# p3-001.net
KiCad netlist of a schematic drawn in EAGLE
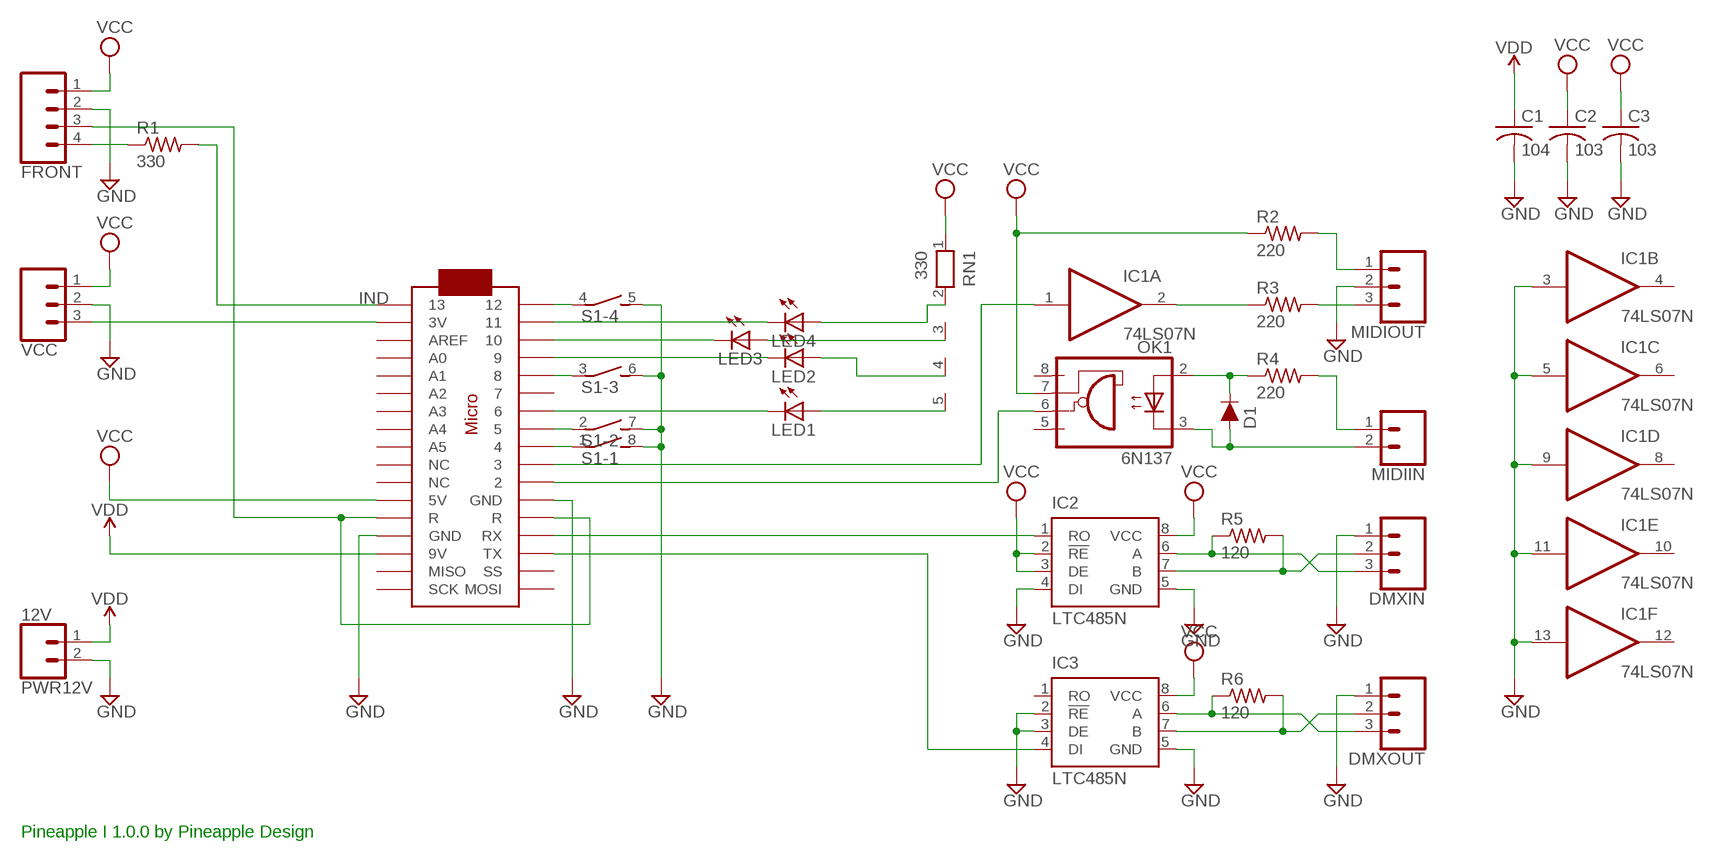
[diagram p0: schematic, sheet 1]

(export (version "E")
  (design (tool "Eeschema 10.0.6"))
  (components
    (comp (ref "C1")
      (value "104")
      (footprint "eagle-import:C025-025X050")
      (libsource (lib "eagle-import") (part "C-US025-025X050"))
    )
    (comp (ref "C2")
      (value "103")
      (footprint "eagle-import:C025-025X050")
      (libsource (lib "eagle-import") (part "C-US025-025X050"))
    )
    (comp (ref "C3")
      (value "103")
      (footprint "eagle-import:C025-025X050")
      (libsource (lib "eagle-import") (part "C-US025-025X050"))
    )
    (comp (ref "D1")
      (value "DIODE-1N4148")
      (footprint "eagle-import:DIODE-1N4148")
      (libsource (lib "eagle-import") (part "DIODE-1N4148"))
    )
    (comp (ref "DMXIN")
      (value "CONN_03JST-PTH")
      (footprint "eagle-import:JST-3-PTH")
      (libsource (lib "eagle-import") (part "CONN_03JST-PTH"))
    )
    (comp (ref "DMXOUT")
      (value "CONN_03JST-PTH")
      (footprint "eagle-import:JST-3-PTH")
      (libsource (lib "eagle-import") (part "CONN_03JST-PTH"))
    )
    (comp (ref "FRONT")
      (value "CONN_04JST-PTH")
      (footprint "eagle-import:JST-4-PTH")
      (libsource (lib "eagle-import") (part "CONN_04JST-PTH"))
    )
    (comp (ref "IC1")
      (value "74LS07N")
      (footprint "eagle-import:DIL14")
      (libsource (lib "eagle-import") (part "7407NLS"))
    )
    (comp (ref "IC2")
      (value "LTC485N")
      (footprint "eagle-import:DIL08")
      (libsource (lib "eagle-import") (part "LTC485N"))
    )
    (comp (ref "IC3")
      (value "LTC485N")
      (footprint "eagle-import:DIL08")
      (libsource (lib "eagle-import") (part "LTC485N"))
    )
    (comp (ref "LED1")
      (value "LED3MM")
      (footprint "eagle-import:LED3MM")
      (libsource (lib "eagle-import") (part "LED3MM"))
    )
    (comp (ref "LED2")
      (value "LED3MM")
      (footprint "eagle-import:LED3MM")
      (libsource (lib "eagle-import") (part "LED3MM"))
    )
    (comp (ref "LED3")
      (value "LED3MM")
      (footprint "eagle-import:LED3MM")
      (libsource (lib "eagle-import") (part "LED3MM"))
    )
    (comp (ref "LED4")
      (value "LED3MM")
      (footprint "eagle-import:LED3MM")
      (libsource (lib "eagle-import") (part "LED3MM"))
    )
    (comp (ref "MIDIIN")
      (value "CONN_02JST-PTH-2")
      (footprint "eagle-import:JST-2-PTH")
      (libsource (lib "eagle-import") (part "CONN_02JST-PTH-2"))
    )
    (comp (ref "MIDIOUT")
      (value "CONN_03JST-PTH")
      (footprint "eagle-import:JST-3-PTH")
      (libsource (lib "eagle-import") (part "CONN_03JST-PTH"))
    )
    (comp (ref "OK1")
      (value "6N137")
      (footprint "eagle-import:DIL08")
      (libsource (lib "eagle-import") (part "6N137"))
    )
    (comp (ref "PWR12V")
      (value "12V")
      (footprint "eagle-import:JST-2-PTH")
      (libsource (lib "eagle-import") (part "CONN_02JST-PTH-2"))
    )
    (comp (ref "R1")
      (value "330")
      (footprint "eagle-import:0204_5")
      (libsource (lib "eagle-import") (part "R-US_0204/5"))
    )
    (comp (ref "R2")
      (value "220")
      (footprint "eagle-import:0204_5")
      (libsource (lib "eagle-import") (part "R-US_0204/5"))
    )
    (comp (ref "R3")
      (value "220")
      (footprint "eagle-import:0204_5")
      (libsource (lib "eagle-import") (part "R-US_0204/5"))
    )
    (comp (ref "R4")
      (value "220")
      (footprint "eagle-import:0204_5")
      (libsource (lib "eagle-import") (part "R-US_0204/5"))
    )
    (comp (ref "R5")
      (value "120")
      (footprint "eagle-import:0204_5")
      (libsource (lib "eagle-import") (part "R-US_0204/5"))
    )
    (comp (ref "R6")
      (value "120")
      (footprint "eagle-import:0204_5")
      (libsource (lib "eagle-import") (part "R-US_0204/5"))
    )
    (comp (ref "RN1")
      (value "330")
      (footprint "eagle-import:RN-5")
      (libsource (lib "eagle-import") (part "RN04"))
    )
    (comp (ref "S1")
      (value "DIP04S")
      (footprint "eagle-import:DIP04S")
      (libsource (lib "eagle-import") (part "DIP04S"))
    )
    (comp (ref "U$1")
      (value "ARDUINOMICRO")
      (footprint "eagle-import:ARDUINOMICRO")
      (libsource (lib "eagle-import") (part "ARDUINOMICRO"))
    )
    (comp (ref "VCC")
      (value "CONN_03JST-PTH")
      (footprint "eagle-import:JST-3-PTH")
      (libsource (lib "eagle-import") (part "SparkFun-Connectors_513_CONN_03JST-PTH"))
    )
  )
  (nets
    (net (code "1") (name "/IND") (class "Default")
      (node (ref "R1") (pin "2") (pinfunction "2_2") (pintype "passive"))
      (node (ref "U$1") (pin "P$34") (pinfunction "13_P$34") (pintype "bidirectional"))
    )
    (net (code "2") (name "GND") (class "Default")
      (node (ref "C1") (pin "2") (pinfunction "2_2") (pintype "passive"))
      (node (ref "C2") (pin "2") (pinfunction "2_2") (pintype "passive"))
      (node (ref "C3") (pin "2") (pinfunction "2_2") (pintype "passive"))
      (node (ref "DMXIN") (pin "1") (pinfunction "1_1") (pintype "passive"))
      (node (ref "DMXOUT") (pin "1") (pinfunction "1_1") (pintype "passive"))
      (node (ref "FRONT") (pin "2") (pinfunction "2_2") (pintype "passive"))
      (node (ref "IC1") (pin "11") (pinfunction "I_11") (pintype "input"))
      (node (ref "IC1") (pin "13") (pinfunction "I_13") (pintype "input"))
      (node (ref "IC1") (pin "3") (pinfunction "I_3") (pintype "input"))
      (node (ref "IC1") (pin "5") (pinfunction "I_5") (pintype "input"))
      (node (ref "IC1") (pin "9") (pinfunction "I_9") (pintype "input"))
      (node (ref "IC2") (pin "4") (pinfunction "DI_4") (pintype "input"))
      (node (ref "IC2") (pin "5") (pinfunction "GND_5") (pintype "input"))
      (node (ref "IC3") (pin "2") (pinfunction "~{RE}_2") (pintype "input"))
      (node (ref "IC3") (pin "3") (pinfunction "DE_3") (pintype "input"))
      (node (ref "IC3") (pin "5") (pinfunction "GND_5") (pintype "input"))
      (node (ref "MIDIOUT") (pin "2") (pinfunction "2_2") (pintype "passive"))
      (node (ref "PWR12V") (pin "2") (pinfunction "2_2") (pintype "passive"))
      (node (ref "S1") (pin "5") (pinfunction "2_5") (pintype "passive"))
      (node (ref "S1") (pin "6") (pinfunction "2_6") (pintype "passive"))
      (node (ref "S1") (pin "7") (pinfunction "2_7") (pintype "passive"))
      (node (ref "S1") (pin "8") (pinfunction "2_8") (pintype "passive"))
      (node (ref "U$1") (pin "P$12") (pinfunction "GND_P$12") (pintype "bidirectional"))
      (node (ref "U$1") (pin "P$21") (pinfunction "GND_P$21") (pintype "bidirectional"))
      (node (ref "VCC") (pin "2") (pinfunction "2_2") (pintype "passive"))
    )
    (net (code "3") (name "Net-(FRONT-Pad3)") (class "Default")
      (node (ref "FRONT") (pin "3") (pinfunction "3_3") (pintype "passive"))
      (node (ref "U$1") (pin "P$13") (pinfunction "R_P$13") (pintype "bidirectional"))
      (node (ref "U$1") (pin "P$22") (pinfunction "R_P$22") (pintype "bidirectional"))
    )
    (net (code "4") (name "Net-(FRONT-Pad4)") (class "Default")
      (node (ref "FRONT") (pin "4") (pinfunction "4_4") (pintype "passive"))
      (node (ref "R1") (pin "1") (pinfunction "1_1") (pintype "passive"))
    )
    (net (code "5") (name "Net-(IC1A-I)") (class "Default")
      (node (ref "IC1") (pin "1") (pinfunction "I_1") (pintype "input"))
      (node (ref "U$1") (pin "P$10") (pinfunction "3_P$10") (pintype "bidirectional"))
    )
    (net (code "6") (name "Net-(IC1A-O)") (class "Default")
      (node (ref "IC1") (pin "2") (pinfunction "O_2") (pintype "open_collector"))
      (node (ref "R3") (pin "1") (pinfunction "1_1") (pintype "passive"))
    )
    (net (code "7") (name "Net-(IC2-A)") (class "Default")
      (node (ref "DMXIN") (pin "3") (pinfunction "3_3") (pintype "passive"))
      (node (ref "IC2") (pin "6") (pinfunction "A_6") (pintype "bidirectional"))
      (node (ref "R5") (pin "1") (pinfunction "1_1") (pintype "passive"))
    )
    (net (code "8") (name "Net-(IC2-B)") (class "Default")
      (node (ref "DMXIN") (pin "2") (pinfunction "2_2") (pintype "passive"))
      (node (ref "IC2") (pin "7") (pinfunction "B_7") (pintype "bidirectional"))
      (node (ref "R5") (pin "2") (pinfunction "2_2") (pintype "passive"))
    )
    (net (code "9") (name "Net-(IC2-RO)") (class "Default")
      (node (ref "IC2") (pin "1") (pinfunction "RO_1") (pintype "output"))
      (node (ref "U$1") (pin "P$14") (pinfunction "RX_P$14") (pintype "bidirectional"))
    )
    (net (code "10") (name "Net-(IC3-A)") (class "Default")
      (node (ref "DMXOUT") (pin "3") (pinfunction "3_3") (pintype "passive"))
      (node (ref "IC3") (pin "6") (pinfunction "A_6") (pintype "bidirectional"))
      (node (ref "R6") (pin "1") (pinfunction "1_1") (pintype "passive"))
    )
    (net (code "11") (name "Net-(IC3-B)") (class "Default")
      (node (ref "DMXOUT") (pin "2") (pinfunction "2_2") (pintype "passive"))
      (node (ref "IC3") (pin "7") (pinfunction "B_7") (pintype "bidirectional"))
      (node (ref "R6") (pin "2") (pinfunction "2_2") (pintype "passive"))
    )
    (net (code "12") (name "Net-(IC3-DI)") (class "Default")
      (node (ref "IC3") (pin "4") (pinfunction "DI_4") (pintype "input"))
      (node (ref "U$1") (pin "P$15") (pinfunction "TX_P$15") (pintype "bidirectional"))
    )
    (net (code "13") (name "Net-(LED1-C)") (class "Default")
      (node (ref "LED1") (pin "K") (pinfunction "C_K") (pintype "passive"))
      (node (ref "U$1") (pin "P$7") (pinfunction "6_P$7") (pintype "bidirectional"))
    )
    (net (code "14") (name "Net-(LED1-PadA)") (class "Default")
      (node (ref "LED1") (pin "A") (pinfunction "A_A") (pintype "passive"))
      (node (ref "RN1") (pin "5") (pinfunction "5_5") (pintype "passive"))
    )
    (net (code "15") (name "Net-(LED2-C)") (class "Default")
      (node (ref "LED2") (pin "K") (pinfunction "C_K") (pintype "passive"))
      (node (ref "U$1") (pin "P$4") (pinfunction "9_P$4") (pintype "bidirectional"))
    )
    (net (code "16") (name "Net-(LED2-PadA)") (class "Default")
      (node (ref "LED2") (pin "A") (pinfunction "A_A") (pintype "passive"))
      (node (ref "RN1") (pin "4") (pinfunction "4_4") (pintype "passive"))
    )
    (net (code "17") (name "Net-(LED3-C)") (class "Default")
      (node (ref "LED3") (pin "K") (pinfunction "C_K") (pintype "passive"))
      (node (ref "U$1") (pin "P$3") (pinfunction "10_P$3") (pintype "bidirectional"))
    )
    (net (code "18") (name "Net-(LED3-PadA)") (class "Default")
      (node (ref "LED3") (pin "A") (pinfunction "A_A") (pintype "passive"))
      (node (ref "RN1") (pin "3") (pinfunction "3_3") (pintype "passive"))
    )
    (net (code "19") (name "Net-(LED4-C)") (class "Default")
      (node (ref "LED4") (pin "K") (pinfunction "C_K") (pintype "passive"))
      (node (ref "U$1") (pin "P$2") (pinfunction "11_P$2") (pintype "bidirectional"))
    )
    (net (code "20") (name "Net-(LED4-PadA)") (class "Default")
      (node (ref "LED4") (pin "A") (pinfunction "A_A") (pintype "passive"))
      (node (ref "RN1") (pin "2") (pinfunction "2_2") (pintype "passive"))
    )
    (net (code "21") (name "Net-(MIDIIN-Pad1)") (class "Default")
      (node (ref "MIDIIN") (pin "1") (pinfunction "1_1") (pintype "passive"))
      (node (ref "R4") (pin "2") (pinfunction "2_2") (pintype "passive"))
    )
    (net (code "22") (name "Net-(MIDIOUT-Pad1)") (class "Default")
      (node (ref "MIDIOUT") (pin "1") (pinfunction "1_1") (pintype "passive"))
      (node (ref "R2") (pin "2") (pinfunction "2_2") (pintype "passive"))
    )
    (net (code "23") (name "Net-(MIDIOUT-Pad3)") (class "Default")
      (node (ref "MIDIOUT") (pin "3") (pinfunction "3_3") (pintype "passive"))
      (node (ref "R3") (pin "2") (pinfunction "2_2") (pintype "passive"))
    )
    (net (code "24") (name "Net-(OK1-A)") (class "Default")
      (node (ref "D1") (pin "C") (pinfunction "C_C") (pintype "passive"))
      (node (ref "OK1") (pin "2") (pinfunction "A_2") (pintype "passive"))
      (node (ref "R4") (pin "1") (pinfunction "1_1") (pintype "passive"))
    )
    (net (code "25") (name "Net-(OK1-C)") (class "Default")
      (node (ref "D1") (pin "A") (pinfunction "A_A") (pintype "passive"))
      (node (ref "MIDIIN") (pin "2") (pinfunction "2_2") (pintype "passive"))
      (node (ref "OK1") (pin "3") (pinfunction "C_3") (pintype "passive"))
    )
    (net (code "26") (name "Net-(OK1-VO)") (class "Default")
      (node (ref "OK1") (pin "6") (pinfunction "VO_6") (pintype "passive"))
      (node (ref "U$1") (pin "P$11") (pinfunction "2_P$11") (pintype "bidirectional"))
    )
    (net (code "27") (name "Net-(S1B-1)") (class "Default")
      (node (ref "S1") (pin "2") (pinfunction "1_2") (pintype "passive"))
      (node (ref "U$1") (pin "P$8") (pinfunction "5_P$8") (pintype "bidirectional"))
    )
    (net (code "28") (name "Net-(S1C-1)") (class "Default")
      (node (ref "S1") (pin "3") (pinfunction "1_3") (pintype "passive"))
      (node (ref "U$1") (pin "P$5") (pinfunction "8_P$5") (pintype "bidirectional"))
    )
    (net (code "29") (name "Net-(S1D-1)") (class "Default")
      (node (ref "S1") (pin "4") (pinfunction "1_4") (pintype "passive"))
      (node (ref "U$1") (pin "P$1") (pinfunction "12_P$1") (pintype "bidirectional"))
    )
    (net (code "30") (name "Net-(U$1-3V)") (class "Default")
      (node (ref "U$1") (pin "P$33") (pinfunction "3V_P$33") (pintype "bidirectional"))
      (node (ref "VCC") (pin "3") (pinfunction "3_3") (pintype "passive"))
    )
    (net (code "31") (name "Net-(U$1-4)") (class "Default")
      (node (ref "S1") (pin "1") (pinfunction "1_1") (pintype "passive"))
      (node (ref "U$1") (pin "P$9") (pinfunction "4_P$9") (pintype "bidirectional"))
    )
    (net (code "32") (name "VCC") (class "Default")
      (node (ref "C2") (pin "1") (pinfunction "1_1") (pintype "passive"))
      (node (ref "C3") (pin "1") (pinfunction "1_1") (pintype "passive"))
      (node (ref "FRONT") (pin "1") (pinfunction "1_1") (pintype "passive"))
      (node (ref "IC2") (pin "2") (pinfunction "~{RE}_2") (pintype "input"))
      (node (ref "IC2") (pin "3") (pinfunction "DE_3") (pintype "input"))
      (node (ref "IC2") (pin "8") (pinfunction "VCC_8") (pintype "input"))
      (node (ref "IC3") (pin "8") (pinfunction "VCC_8") (pintype "input"))
      (node (ref "OK1") (pin "7") (pinfunction "VE_7") (pintype "passive"))
      (node (ref "R2") (pin "1") (pinfunction "1_1") (pintype "passive"))
      (node (ref "RN1") (pin "1") (pinfunction "1_1") (pintype "passive"))
      (node (ref "U$1") (pin "P$23") (pinfunction "5V_P$23") (pintype "bidirectional"))
      (node (ref "VCC") (pin "1") (pinfunction "1_1") (pintype "passive"))
    )
    (net (code "33") (name "VDD") (class "Default")
      (node (ref "C1") (pin "1") (pinfunction "1_1") (pintype "passive"))
      (node (ref "PWR12V") (pin "1") (pinfunction "1_1") (pintype "passive"))
      (node (ref "U$1") (pin "P$20") (pinfunction "9V_P$20") (pintype "bidirectional"))
    )
    (net (code "34") (name "unconnected-(IC1B-O-Pad4)") (class "Default")
      (node (ref "IC1") (pin "4") (pinfunction "O_4") (pintype "open_collector"))
    )
    (net (code "35") (name "unconnected-(IC1C-O-Pad6)") (class "Default")
      (node (ref "IC1") (pin "6") (pinfunction "O_6") (pintype "open_collector"))
    )
    (net (code "36") (name "unconnected-(IC1D-O-Pad8)") (class "Default")
      (node (ref "IC1") (pin "8") (pinfunction "O_8") (pintype "open_collector"))
    )
    (net (code "37") (name "unconnected-(IC1E-O-Pad10)") (class "Default")
      (node (ref "IC1") (pin "10") (pinfunction "O_10") (pintype "open_collector"))
    )
    (net (code "38") (name "unconnected-(IC1F-O-Pad12)") (class "Default")
      (node (ref "IC1") (pin "12") (pinfunction "O_12") (pintype "open_collector"))
    )
    (net (code "39") (name "unconnected-(IC3-RO-Pad1)") (class "Default")
      (node (ref "IC3") (pin "1") (pinfunction "RO_1") (pintype "output"))
    )
    (net (code "40") (name "unconnected-(OK1-GND-Pad5)") (class "Default")
      (node (ref "OK1") (pin "5") (pinfunction "GND_5") (pintype "passive"))
    )
    (net (code "41") (name "unconnected-(OK1-VCC-Pad8)") (class "Default")
      (node (ref "OK1") (pin "8") (pinfunction "VCC_8") (pintype "passive"))
    )
    (net (code "42") (name "unconnected-(U$1-7-PadP$6)") (class "Default")
      (node (ref "U$1") (pin "P$6") (pinfunction "7_P$6") (pintype "bidirectional"))
    )
    (net (code "43") (name "unconnected-(U$1-A0-PadP$31)") (class "Default")
      (node (ref "U$1") (pin "P$31") (pinfunction "A0_P$31") (pintype "bidirectional"))
    )
    (net (code "44") (name "unconnected-(U$1-A1-PadP$30)") (class "Default")
      (node (ref "U$1") (pin "P$30") (pinfunction "A1_P$30") (pintype "bidirectional"))
    )
    (net (code "45") (name "unconnected-(U$1-A2-PadP$29)") (class "Default")
      (node (ref "U$1") (pin "P$29") (pinfunction "A2_P$29") (pintype "bidirectional"))
    )
    (net (code "46") (name "unconnected-(U$1-A3-PadP$28)") (class "Default")
      (node (ref "U$1") (pin "P$28") (pinfunction "A3_P$28") (pintype "bidirectional"))
    )
    (net (code "47") (name "unconnected-(U$1-A4-PadP$27)") (class "Default")
      (node (ref "U$1") (pin "P$27") (pinfunction "A4_P$27") (pintype "bidirectional"))
    )
    (net (code "48") (name "unconnected-(U$1-A5-PadP$26)") (class "Default")
      (node (ref "U$1") (pin "P$26") (pinfunction "A5_P$26") (pintype "bidirectional"))
    )
    (net (code "49") (name "unconnected-(U$1-AREF-PadP$32)") (class "Default")
      (node (ref "U$1") (pin "P$32") (pinfunction "AREF_P$32") (pintype "bidirectional"))
    )
    (net (code "50") (name "unconnected-(U$1-MISO-PadP$19)") (class "Default")
      (node (ref "U$1") (pin "P$19") (pinfunction "MISO_P$19") (pintype "bidirectional"))
    )
    (net (code "51") (name "unconnected-(U$1-MOSI-PadP$17)") (class "Default")
      (node (ref "U$1") (pin "P$17") (pinfunction "MOSI_P$17") (pintype "bidirectional"))
    )
    (net (code "52") (name "unconnected-(U$1-NC-PadP$24)") (class "Default")
      (node (ref "U$1") (pin "P$24") (pinfunction "NC_P$24") (pintype "bidirectional"))
    )
    (net (code "53") (name "unconnected-(U$1-NC-PadP$25)") (class "Default")
      (node (ref "U$1") (pin "P$25") (pinfunction "NC_P$25") (pintype "bidirectional"))
    )
    (net (code "54") (name "unconnected-(U$1-SCK-PadP$18)") (class "Default")
      (node (ref "U$1") (pin "P$18") (pinfunction "SCK_P$18") (pintype "bidirectional"))
    )
    (net (code "55") (name "unconnected-(U$1-SS-PadP$16)") (class "Default")
      (node (ref "U$1") (pin "P$16") (pinfunction "SS_P$16") (pintype "bidirectional"))
    )
  )
)
